# inwich.net
KiCad netlist of a schematic drawn in EAGLE
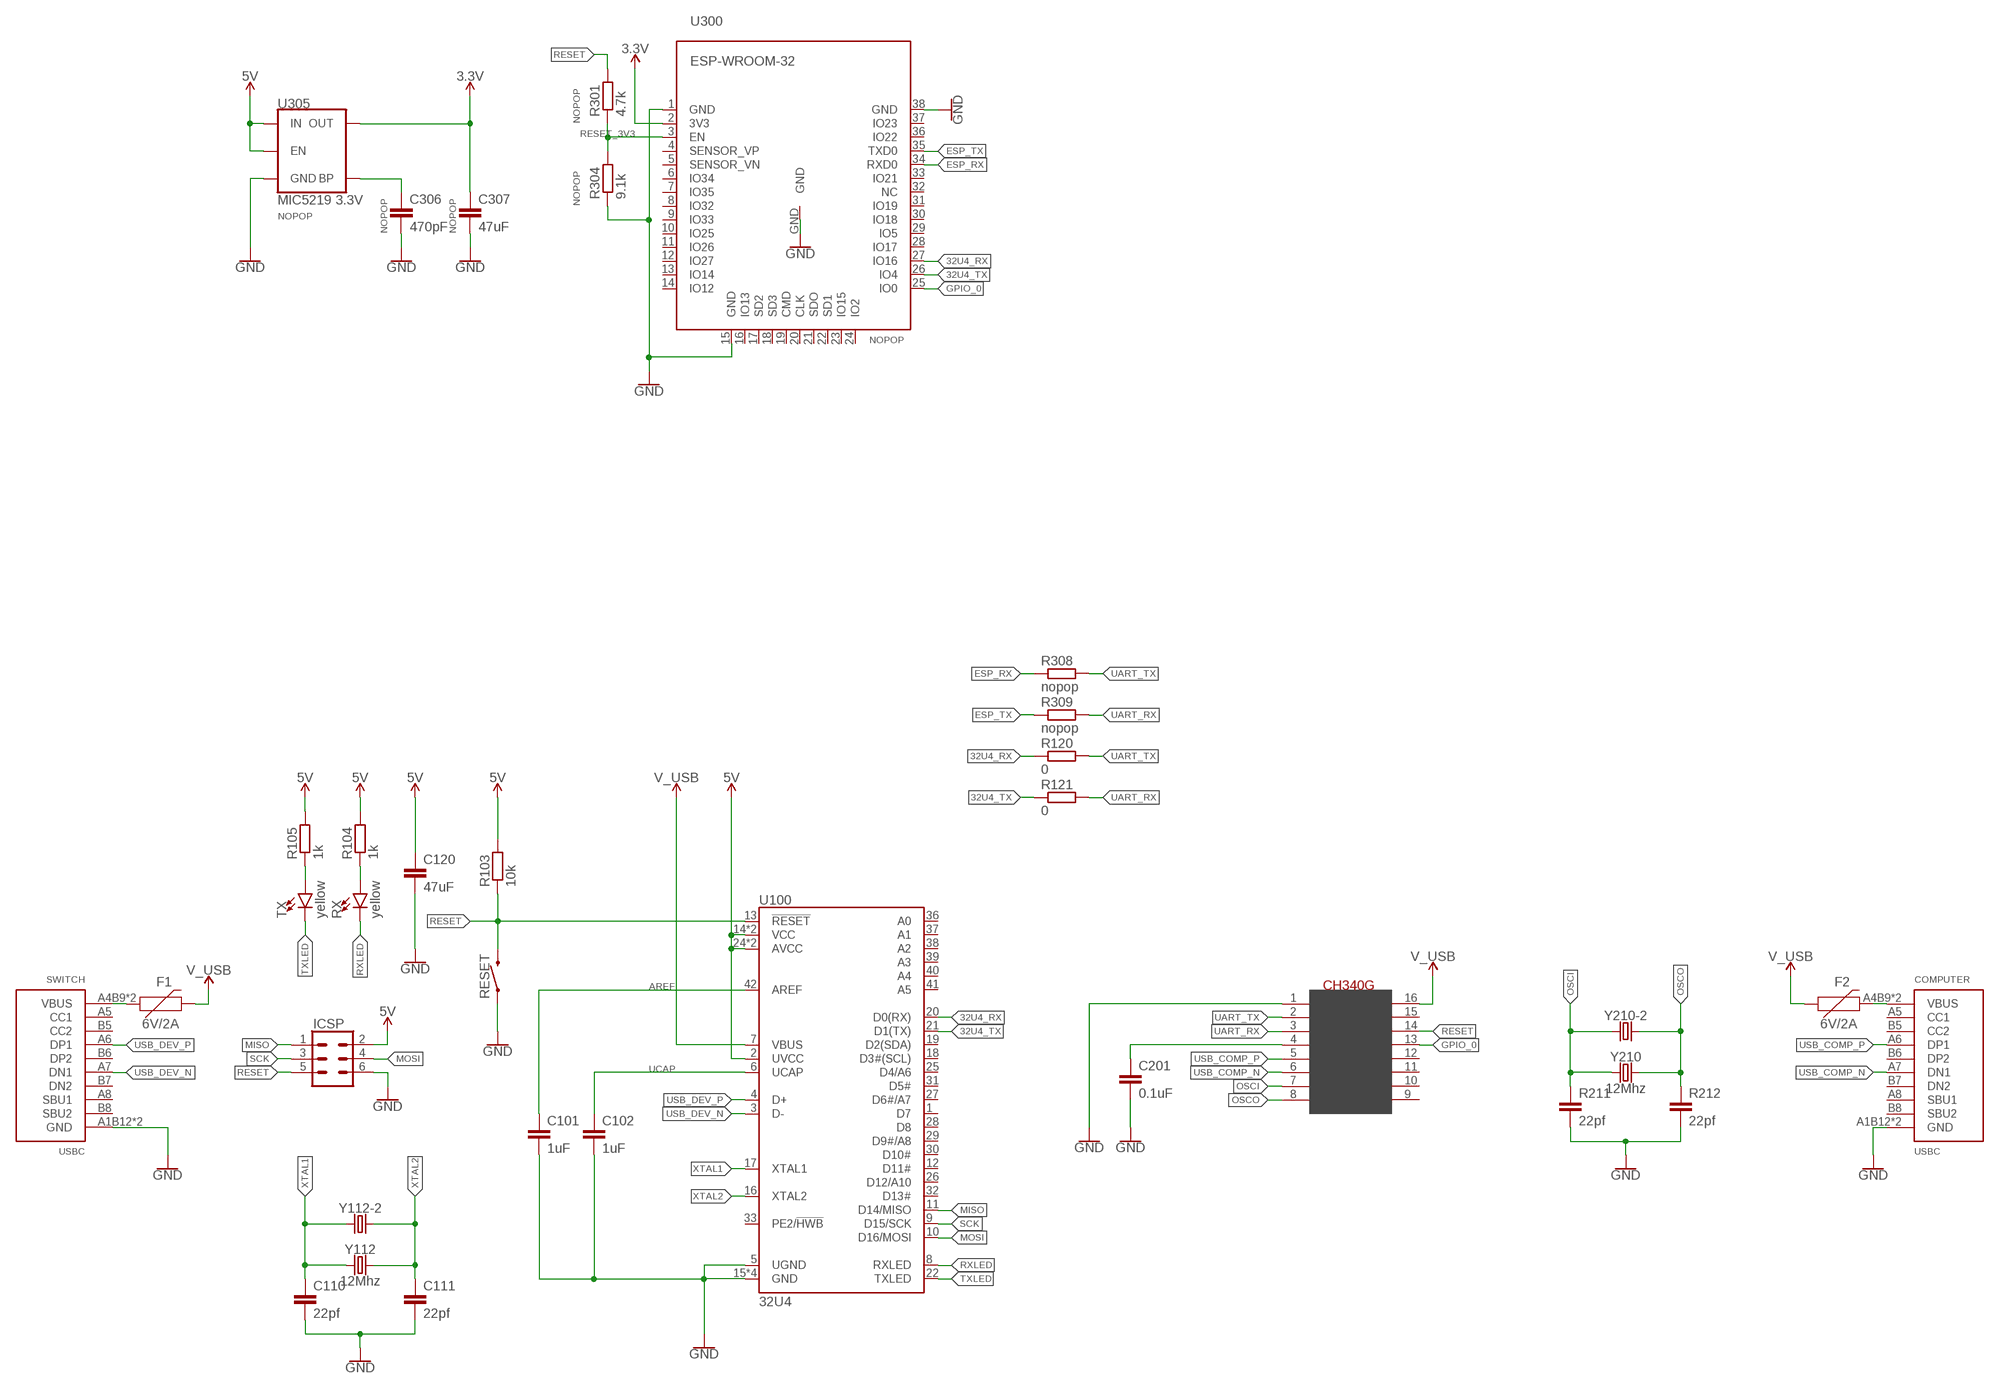
[diagram p0: schematic, sheet 1]

(export (version "E")
  (design (tool "Eeschema 10.0.6"))
  (components
    (comp (ref "C101")
      (value "1uF")
      (footprint "eagle-import:C0805")
      (libsource (lib "eagle-import") (part "C-EUC0805"))
    )
    (comp (ref "C102")
      (value "1uF")
      (footprint "eagle-import:C0805")
      (libsource (lib "eagle-import") (part "C-EUC0805"))
    )
    (comp (ref "C110")
      (value "22pf")
      (footprint "eagle-import:C0805")
      (libsource (lib "eagle-import") (part "C-EUC0805"))
    )
    (comp (ref "C111")
      (value "22pf")
      (footprint "eagle-import:C0805")
      (libsource (lib "eagle-import") (part "C-EUC0805"))
    )
    (comp (ref "C120")
      (value "47uF")
      (footprint "eagle-import:C0805")
      (libsource (lib "eagle-import") (part "C-EUC0805"))
    )
    (comp (ref "C201")
      (value "0.1uF")
      (footprint "eagle-import:C0805")
      (libsource (lib "eagle-import") (part "C-EUC0805"))
    )
    (comp (ref "C306")
      (value "470pF")
      (footprint "eagle-import:C0805")
      (libsource (lib "eagle-import") (part "C-EUC0805"))
    )
    (comp (ref "C307")
      (value "47uF")
      (footprint "eagle-import:C0805")
      (libsource (lib "eagle-import") (part "C-EUC0805"))
    )
    (comp (ref "COMPUTER")
      (value "USBC")
      (footprint "eagle-import:USBC")
      (libsource (lib "eagle-import") (part "USBC"))
    )
    (comp (ref "F1")
      (value "6V/2A")
      (footprint "eagle-import:1210")
      (libsource (lib "eagle-import") (part "PPTC_6V2A"))
    )
    (comp (ref "F2")
      (value "6V/2A")
      (footprint "eagle-import:1210")
      (libsource (lib "eagle-import") (part "PPTC_6V2A"))
    )
    (comp (ref "ICSP")
      (value "CONN_03X2SHROUD")
      (footprint "eagle-import:2X3-SHROUDED")
      (libsource (lib "eagle-import") (part "CONN_03X2SHROUD"))
    )
    (comp (ref "R103")
      (value "10k")
      (footprint "eagle-import:R0805")
      (libsource (lib "eagle-import") (part "R-EU_R0805"))
    )
    (comp (ref "R104")
      (value "1k")
      (footprint "eagle-import:R0805")
      (libsource (lib "eagle-import") (part "R-EU_R0805"))
    )
    (comp (ref "R105")
      (value "1k")
      (footprint "eagle-import:R0805")
      (libsource (lib "eagle-import") (part "R-EU_R0805"))
    )
    (comp (ref "R120")
      (value "0")
      (footprint "eagle-import:R0805")
      (libsource (lib "eagle-import") (part "R-EU_R0805"))
    )
    (comp (ref "R121")
      (value "0")
      (footprint "eagle-import:R0805")
      (libsource (lib "eagle-import") (part "R-EU_R0805"))
    )
    (comp (ref "R211")
      (value "22pf")
      (footprint "eagle-import:C0805")
      (libsource (lib "eagle-import") (part "C-EUC0805"))
    )
    (comp (ref "R212")
      (value "22pf")
      (footprint "eagle-import:C0805")
      (libsource (lib "eagle-import") (part "C-EUC0805"))
    )
    (comp (ref "R301")
      (value "4.7k")
      (footprint "eagle-import:R0805")
      (libsource (lib "eagle-import") (part "R-EU_R0805"))
    )
    (comp (ref "R304")
      (value "9.1k")
      (footprint "eagle-import:R0805")
      (libsource (lib "eagle-import") (part "R-EU_R0805"))
    )
    (comp (ref "R308")
      (value "nopop")
      (footprint "eagle-import:R0805")
      (libsource (lib "eagle-import") (part "R-EU_R0805"))
    )
    (comp (ref "R309")
      (value "nopop")
      (footprint "eagle-import:R0805")
      (libsource (lib "eagle-import") (part "R-EU_R0805"))
    )
    (comp (ref "RESET")
      (value "MOMENTARY-SWITCH-SPST-SMD-6.0X3.5MM")
      (footprint "eagle-import:TACTILE_SWITCH_SMD_6.0X3.5MM")
      (libsource (lib "eagle-import") (part "MOMENTARY-SWITCH-SPST-SMD-6.0X3.5MM"))
    )
    (comp (ref "RX")
      (value "yellow")
      (footprint "eagle-import:LED-1206")
      (libsource (lib "eagle-import") (part "LED1206"))
    )
    (comp (ref "SWITCH")
      (value "USBC")
      (footprint "eagle-import:USBC")
      (libsource (lib "eagle-import") (part "USBC"))
    )
    (comp (ref "TX")
      (value "yellow")
      (footprint "eagle-import:LED-1206")
      (libsource (lib "eagle-import") (part "LED1206"))
    )
    (comp (ref "U100")
      (value "32U4")
      (footprint "eagle-import:TQFP44")
      (libsource (lib "eagle-import") (part "ATMEGA32U4-ARDUINOTQFP-44"))
    )
    (comp (ref "U200")
      (value "CH340G")
      (footprint "eagle-import:SOIC16")
      (libsource (lib "eagle-import") (part "CH340G"))
    )
    (comp (ref "U300")
      (value "ESP-WROOM-32")
      (footprint "eagle-import:ESP-WROOM-32")
      (libsource (lib "eagle-import") (part "ESP-WROOM-32"))
    )
    (comp (ref "U305")
      (value "MIC5219 3.3V")
      (footprint "eagle-import:SOT23-5")
      (libsource (lib "eagle-import") (part "V_REG_MIC52193.3V"))
    )
    (comp (ref "Y112")
      (value "12Mhz")
      (footprint "eagle-import:HC49UP")
      (libsource (lib "eagle-import") (part "CRYSTALSMD-HC49UP"))
    )
    (comp (ref "Y112-2")
      (value "CRYSTALPTH-HC49UV")
      (footprint "eagle-import:HC49U")
      (libsource (lib "eagle-import") (part "CRYSTALPTH-HC49UV"))
    )
    (comp (ref "Y210")
      (value "12Mhz")
      (footprint "eagle-import:HC49UP")
      (libsource (lib "eagle-import") (part "CRYSTALSMD-HC49UP"))
    )
    (comp (ref "Y210-2")
      (value "CRYSTALPTH-HC49UV")
      (footprint "eagle-import:HC49U")
      (libsource (lib "eagle-import") (part "CRYSTALPTH-HC49UV"))
    )
  )
  (nets
    (net (code "1") (name "/AREF") (class "Default")
      (node (ref "C101") (pin "1") (pinfunction "1_1") (pintype "passive"))
      (node (ref "U100") (pin "42") (pinfunction "AREF_42") (pintype "bidirectional"))
    )
    (net (code "2") (name "/RESET_3V3") (class "Default")
      (node (ref "R301") (pin "1") (pinfunction "1_1") (pintype "passive"))
      (node (ref "R304") (pin "2") (pinfunction "2_2") (pintype "passive"))
      (node (ref "U300") (pin "3") (pinfunction "EN_3") (pintype "bidirectional"))
    )
    (net (code "3") (name "/UCAP") (class "Default")
      (node (ref "C102") (pin "1") (pinfunction "1_1") (pintype "passive"))
      (node (ref "U100") (pin "6") (pinfunction "UCAP_6") (pintype "bidirectional"))
    )
    (net (code "4") (name "3.3V") (class "Default")
      (node (ref "C307") (pin "1") (pinfunction "1_1") (pintype "passive"))
      (node (ref "U300") (pin "2") (pinfunction "3V3_2") (pintype "bidirectional"))
      (node (ref "U305") (pin "5") (pinfunction "OUT_5") (pintype "passive"))
    )
    (net (code "5") (name "5V") (class "Default")
      (node (ref "C120") (pin "1") (pinfunction "1_1") (pintype "passive"))
      (node (ref "ICSP") (pin "2") (pinfunction "2_2") (pintype "bidirectional"))
      (node (ref "R103") (pin "2") (pinfunction "2_2") (pintype "passive"))
      (node (ref "R104") (pin "2") (pinfunction "2_2") (pintype "passive"))
      (node (ref "R105") (pin "2") (pinfunction "2_2") (pintype "passive"))
      (node (ref "U100") (pin "14") (pinfunction "VCC_14") (pintype "bidirectional"))
      (node (ref "U100") (pin "2") (pinfunction "UVCC_2") (pintype "bidirectional"))
      (node (ref "U100") (pin "24") (pinfunction "AVCC_24") (pintype "bidirectional"))
      (node (ref "U100") (pin "34") (pinfunction "VCC_34") (pintype "bidirectional"))
      (node (ref "U100") (pin "44") (pinfunction "AVCC_44") (pintype "bidirectional"))
      (node (ref "U305") (pin "1") (pinfunction "IN_1") (pintype "input"))
      (node (ref "U305") (pin "3") (pinfunction "EN_3") (pintype "input"))
    )
    (net (code "6") (name "32U4_RX") (class "Default")
      (node (ref "R120") (pin "1") (pinfunction "1_1") (pintype "passive"))
      (node (ref "U100") (pin "20") (pinfunction "D0(RX)_20") (pintype "bidirectional"))
      (node (ref "U300") (pin "27") (pinfunction "IO16_27") (pintype "bidirectional"))
    )
    (net (code "7") (name "32U4_TX") (class "Default")
      (node (ref "R121") (pin "1") (pinfunction "1_1") (pintype "passive"))
      (node (ref "U100") (pin "21") (pinfunction "D1(TX)_21") (pintype "bidirectional"))
      (node (ref "U300") (pin "26") (pinfunction "IO4_26") (pintype "bidirectional"))
    )
    (net (code "8") (name "ESP_RX") (class "Default")
      (node (ref "R308") (pin "1") (pinfunction "1_1") (pintype "passive"))
      (node (ref "U300") (pin "34") (pinfunction "RXD0_34") (pintype "bidirectional"))
    )
    (net (code "9") (name "ESP_TX") (class "Default")
      (node (ref "R309") (pin "1") (pinfunction "1_1") (pintype "passive"))
      (node (ref "U300") (pin "35") (pinfunction "TXD0_35") (pintype "bidirectional"))
    )
    (net (code "10") (name "GND") (class "Default")
      (node (ref "C101") (pin "2") (pinfunction "2_2") (pintype "passive"))
      (node (ref "C102") (pin "2") (pinfunction "2_2") (pintype "passive"))
      (node (ref "C110") (pin "2") (pinfunction "2_2") (pintype "passive"))
      (node (ref "C111") (pin "2") (pinfunction "2_2") (pintype "passive"))
      (node (ref "C120") (pin "2") (pinfunction "2_2") (pintype "passive"))
      (node (ref "C201") (pin "2") (pinfunction "2_2") (pintype "passive"))
      (node (ref "C306") (pin "2") (pinfunction "2_2") (pintype "passive"))
      (node (ref "C307") (pin "2") (pinfunction "2_2") (pintype "passive"))
      (node (ref "COMPUTER") (pin "A1B12") (pinfunction "GND_A1B12") (pintype "bidirectional"))
      (node (ref "COMPUTER") (pin "B1A12") (pinfunction "GND_B1A12") (pintype "bidirectional"))
      (node (ref "ICSP") (pin "6") (pinfunction "6_6") (pintype "bidirectional"))
      (node (ref "R211") (pin "2") (pinfunction "2_2") (pintype "passive"))
      (node (ref "R212") (pin "2") (pinfunction "2_2") (pintype "passive"))
      (node (ref "R304") (pin "1") (pinfunction "1_1") (pintype "passive"))
      (node (ref "RESET") (pin "1") (pinfunction "1_1") (pintype "passive"))
      (node (ref "SWITCH") (pin "A1B12") (pinfunction "GND_A1B12") (pintype "bidirectional"))
      (node (ref "SWITCH") (pin "B1A12") (pinfunction "GND_B1A12") (pintype "bidirectional"))
      (node (ref "U100") (pin "15") (pinfunction "GND_15") (pintype "bidirectional"))
      (node (ref "U100") (pin "23") (pinfunction "GND_23") (pintype "bidirectional"))
      (node (ref "U100") (pin "35") (pinfunction "GND_35") (pintype "bidirectional"))
      (node (ref "U100") (pin "43") (pinfunction "GND_43") (pintype "bidirectional"))
      (node (ref "U100") (pin "5") (pinfunction "UGND_5") (pintype "bidirectional"))
      (node (ref "U200") (pin "1") (pinfunction "GND_1") (pintype "bidirectional"))
      (node (ref "U300") (pin "1") (pinfunction "GND_1") (pintype "bidirectional"))
      (node (ref "U300") (pin "15") (pinfunction "GND_15") (pintype "bidirectional"))
      (node (ref "U300") (pin "38") (pinfunction "GND_38") (pintype "bidirectional"))
      (node (ref "U300") (pin "GND") (pinfunction "GND_GND") (pintype "bidirectional"))
      (node (ref "U305") (pin "2") (pinfunction "GND_2") (pintype "input"))
    )
    (net (code "11") (name "GPIO_0") (class "Default")
      (node (ref "U200") (pin "13") (pinfunction "DTR_13") (pintype "bidirectional"))
      (node (ref "U300") (pin "25") (pinfunction "IO0_25") (pintype "bidirectional"))
    )
    (net (code "12") (name "MISO") (class "Default")
      (node (ref "ICSP") (pin "1") (pinfunction "1_1") (pintype "bidirectional"))
      (node (ref "U100") (pin "11") (pinfunction "D14/MISO_11") (pintype "bidirectional"))
    )
    (net (code "13") (name "MOSI") (class "Default")
      (node (ref "ICSP") (pin "4") (pinfunction "4_4") (pintype "bidirectional"))
      (node (ref "U100") (pin "10") (pinfunction "D16/MOSI_10") (pintype "bidirectional"))
    )
    (net (code "14") (name "Net-(COMPUTER-VBUS-PadA4B9)") (class "Default")
      (node (ref "COMPUTER") (pin "A4B9") (pinfunction "VBUS_A4B9") (pintype "bidirectional"))
      (node (ref "COMPUTER") (pin "B4A9") (pinfunction "VBUS_B4A9") (pintype "bidirectional"))
      (node (ref "F2") (pin "2") (pinfunction "2_2") (pintype "bidirectional"))
    )
    (net (code "15") (name "Net-(F1-Pad1)") (class "Default")
      (node (ref "F1") (pin "1") (pinfunction "1_1") (pintype "bidirectional"))
      (node (ref "SWITCH") (pin "A4B9") (pinfunction "VBUS_A4B9") (pintype "bidirectional"))
      (node (ref "SWITCH") (pin "B4A9") (pinfunction "VBUS_B4A9") (pintype "bidirectional"))
    )
    (net (code "16") (name "Net-(R104-Pad1)") (class "Default")
      (node (ref "R104") (pin "1") (pinfunction "1_1") (pintype "passive"))
      (node (ref "RX") (pin "A") (pinfunction "A_A") (pintype "passive"))
    )
    (net (code "17") (name "Net-(R105-Pad1)") (class "Default")
      (node (ref "R105") (pin "1") (pinfunction "1_1") (pintype "passive"))
      (node (ref "TX") (pin "A") (pinfunction "A_A") (pintype "passive"))
    )
    (net (code "18") (name "Net-(U200-V3)") (class "Default")
      (node (ref "C201") (pin "1") (pinfunction "1_1") (pintype "passive"))
      (node (ref "U200") (pin "4") (pinfunction "V3_4") (pintype "bidirectional"))
    )
    (net (code "19") (name "Net-(U305-BP)") (class "Default")
      (node (ref "C306") (pin "1") (pinfunction "1_1") (pintype "passive"))
      (node (ref "U305") (pin "4") (pinfunction "BP_4") (pintype "input"))
    )
    (net (code "20") (name "OSCI") (class "Default")
      (node (ref "R211") (pin "1") (pinfunction "1_1") (pintype "passive"))
      (node (ref "U200") (pin "7") (pinfunction "XI_7") (pintype "bidirectional"))
      (node (ref "Y210") (pin "1") (pinfunction "1_1") (pintype "passive"))
      (node (ref "Y210-2") (pin "1") (pinfunction "1_1") (pintype "passive"))
    )
    (net (code "21") (name "OSCO") (class "Default")
      (node (ref "R212") (pin "1") (pinfunction "1_1") (pintype "passive"))
      (node (ref "U200") (pin "8") (pinfunction "XO_8") (pintype "bidirectional"))
      (node (ref "Y210") (pin "2") (pinfunction "2_2") (pintype "passive"))
      (node (ref "Y210-2") (pin "2") (pinfunction "2_2") (pintype "passive"))
    )
    (net (code "22") (name "RESET") (class "Default")
      (node (ref "ICSP") (pin "5") (pinfunction "5_5") (pintype "bidirectional"))
      (node (ref "R103") (pin "1") (pinfunction "1_1") (pintype "passive"))
      (node (ref "R301") (pin "2") (pinfunction "2_2") (pintype "passive"))
      (node (ref "RESET") (pin "2") (pinfunction "2_2") (pintype "passive"))
      (node (ref "U100") (pin "13") (pinfunction "~{RESET}_13") (pintype "bidirectional"))
      (node (ref "U200") (pin "14") (pinfunction "RTS_14") (pintype "bidirectional"))
    )
    (net (code "23") (name "RXLED") (class "Default")
      (node (ref "RX") (pin "C") (pinfunction "C_C") (pintype "passive"))
      (node (ref "U100") (pin "8") (pinfunction "RXLED_8") (pintype "bidirectional"))
    )
    (net (code "24") (name "SCK") (class "Default")
      (node (ref "ICSP") (pin "3") (pinfunction "3_3") (pintype "bidirectional"))
      (node (ref "U100") (pin "9") (pinfunction "D15/SCK_9") (pintype "bidirectional"))
    )
    (net (code "25") (name "TXLED") (class "Default")
      (node (ref "TX") (pin "C") (pinfunction "C_C") (pintype "passive"))
      (node (ref "U100") (pin "22") (pinfunction "TXLED_22") (pintype "bidirectional"))
    )
    (net (code "26") (name "UART_RX") (class "Default")
      (node (ref "R121") (pin "2") (pinfunction "2_2") (pintype "passive"))
      (node (ref "R309") (pin "2") (pinfunction "2_2") (pintype "passive"))
      (node (ref "U200") (pin "3") (pinfunction "RX_3") (pintype "bidirectional"))
    )
    (net (code "27") (name "UART_TX") (class "Default")
      (node (ref "R120") (pin "2") (pinfunction "2_2") (pintype "passive"))
      (node (ref "R308") (pin "2") (pinfunction "2_2") (pintype "passive"))
      (node (ref "U200") (pin "2") (pinfunction "TX_2") (pintype "bidirectional"))
    )
    (net (code "28") (name "USB_COMP_N") (class "Default")
      (node (ref "COMPUTER") (pin "A7") (pinfunction "DN1_A7") (pintype "bidirectional"))
      (node (ref "U200") (pin "6") (pinfunction "D-_6") (pintype "bidirectional"))
    )
    (net (code "29") (name "USB_COMP_P") (class "Default")
      (node (ref "COMPUTER") (pin "A6") (pinfunction "DP1_A6") (pintype "bidirectional"))
      (node (ref "U200") (pin "5") (pinfunction "D+_5") (pintype "bidirectional"))
    )
    (net (code "30") (name "USB_DEV_N") (class "Default")
      (node (ref "SWITCH") (pin "A7") (pinfunction "DN1_A7") (pintype "bidirectional"))
      (node (ref "U100") (pin "3") (pinfunction "D-_3") (pintype "bidirectional"))
    )
    (net (code "31") (name "USB_DEV_P") (class "Default")
      (node (ref "SWITCH") (pin "A6") (pinfunction "DP1_A6") (pintype "bidirectional"))
      (node (ref "U100") (pin "4") (pinfunction "D+_4") (pintype "bidirectional"))
    )
    (net (code "32") (name "V_USB") (class "Default")
      (node (ref "F1") (pin "2") (pinfunction "2_2") (pintype "bidirectional"))
      (node (ref "F2") (pin "1") (pinfunction "1_1") (pintype "bidirectional"))
      (node (ref "U100") (pin "7") (pinfunction "VBUS_7") (pintype "bidirectional"))
      (node (ref "U200") (pin "16") (pinfunction "VCC_16") (pintype "bidirectional"))
    )
    (net (code "33") (name "XTAL1") (class "Default")
      (node (ref "C110") (pin "1") (pinfunction "1_1") (pintype "passive"))
      (node (ref "U100") (pin "17") (pinfunction "XTAL1_17") (pintype "bidirectional"))
      (node (ref "Y112") (pin "1") (pinfunction "1_1") (pintype "passive"))
      (node (ref "Y112-2") (pin "1") (pinfunction "1_1") (pintype "passive"))
    )
    (net (code "34") (name "XTAL2") (class "Default")
      (node (ref "C111") (pin "1") (pinfunction "1_1") (pintype "passive"))
      (node (ref "U100") (pin "16") (pinfunction "XTAL2_16") (pintype "bidirectional"))
      (node (ref "Y112") (pin "2") (pinfunction "2_2") (pintype "passive"))
      (node (ref "Y112-2") (pin "2") (pinfunction "2_2") (pintype "passive"))
    )
    (net (code "35") (name "unconnected-(COMPUTER-CC1-PadA5)") (class "Default")
      (node (ref "COMPUTER") (pin "A5") (pinfunction "CC1_A5") (pintype "bidirectional"))
    )
    (net (code "36") (name "unconnected-(COMPUTER-CC2-PadB5)") (class "Default")
      (node (ref "COMPUTER") (pin "B5") (pinfunction "CC2_B5") (pintype "bidirectional"))
    )
    (net (code "37") (name "unconnected-(COMPUTER-DN2-PadB7)") (class "Default")
      (node (ref "COMPUTER") (pin "B7") (pinfunction "DN2_B7") (pintype "bidirectional"))
    )
    (net (code "38") (name "unconnected-(COMPUTER-DP2-PadB6)") (class "Default")
      (node (ref "COMPUTER") (pin "B6") (pinfunction "DP2_B6") (pintype "bidirectional"))
    )
    (net (code "39") (name "unconnected-(COMPUTER-SBU1-PadA8)") (class "Default")
      (node (ref "COMPUTER") (pin "A8") (pinfunction "SBU1_A8") (pintype "bidirectional"))
    )
    (net (code "40") (name "unconnected-(COMPUTER-SBU2-PadB8)") (class "Default")
      (node (ref "COMPUTER") (pin "B8") (pinfunction "SBU2_B8") (pintype "bidirectional"))
    )
    (net (code "41") (name "unconnected-(SWITCH-CC1-PadA5)") (class "Default")
      (node (ref "SWITCH") (pin "A5") (pinfunction "CC1_A5") (pintype "bidirectional"))
    )
    (net (code "42") (name "unconnected-(SWITCH-CC2-PadB5)") (class "Default")
      (node (ref "SWITCH") (pin "B5") (pinfunction "CC2_B5") (pintype "bidirectional"))
    )
    (net (code "43") (name "unconnected-(SWITCH-DN2-PadB7)") (class "Default")
      (node (ref "SWITCH") (pin "B7") (pinfunction "DN2_B7") (pintype "bidirectional"))
    )
    (net (code "44") (name "unconnected-(SWITCH-DP2-PadB6)") (class "Default")
      (node (ref "SWITCH") (pin "B6") (pinfunction "DP2_B6") (pintype "bidirectional"))
    )
    (net (code "45") (name "unconnected-(SWITCH-SBU1-PadA8)") (class "Default")
      (node (ref "SWITCH") (pin "A8") (pinfunction "SBU1_A8") (pintype "bidirectional"))
    )
    (net (code "46") (name "unconnected-(SWITCH-SBU2-PadB8)") (class "Default")
      (node (ref "SWITCH") (pin "B8") (pinfunction "SBU2_B8") (pintype "bidirectional"))
    )
    (net (code "47") (name "unconnected-(U100-A0-Pad36)") (class "Default")
      (node (ref "U100") (pin "36") (pinfunction "A0_36") (pintype "bidirectional"))
    )
    (net (code "48") (name "unconnected-(U100-A1-Pad37)") (class "Default")
      (node (ref "U100") (pin "37") (pinfunction "A1_37") (pintype "bidirectional"))
    )
    (net (code "49") (name "unconnected-(U100-A2-Pad38)") (class "Default")
      (node (ref "U100") (pin "38") (pinfunction "A2_38") (pintype "bidirectional"))
    )
    (net (code "50") (name "unconnected-(U100-A3-Pad39)") (class "Default")
      (node (ref "U100") (pin "39") (pinfunction "A3_39") (pintype "bidirectional"))
    )
    (net (code "51") (name "unconnected-(U100-A4-Pad40)") (class "Default")
      (node (ref "U100") (pin "40") (pinfunction "A4_40") (pintype "bidirectional"))
    )
    (net (code "52") (name "unconnected-(U100-A5-Pad41)") (class "Default")
      (node (ref "U100") (pin "41") (pinfunction "A5_41") (pintype "bidirectional"))
    )
    (net (code "53") (name "unconnected-(U100-D2(SDA)-Pad19)") (class "Default")
      (node (ref "U100") (pin "19") (pinfunction "D2(SDA)_19") (pintype "bidirectional"))
    )
    (net (code "54") (name "unconnected-(U100-D3#(SCL)-Pad18)") (class "Default")
      (node (ref "U100") (pin "18") (pinfunction "D3#(SCL)_18") (pintype "bidirectional"))
    )
    (net (code "55") (name "unconnected-(U100-D4{slash}A6-Pad25)") (class "Default")
      (node (ref "U100") (pin "25") (pinfunction "D4/A6_25") (pintype "bidirectional"))
    )
    (net (code "56") (name "unconnected-(U100-D5#-Pad31)") (class "Default")
      (node (ref "U100") (pin "31") (pinfunction "D5#_31") (pintype "bidirectional"))
    )
    (net (code "57") (name "unconnected-(U100-D6#{slash}A7-Pad27)") (class "Default")
      (node (ref "U100") (pin "27") (pinfunction "D6#/A7_27") (pintype "bidirectional"))
    )
    (net (code "58") (name "unconnected-(U100-D7-Pad1)") (class "Default")
      (node (ref "U100") (pin "1") (pinfunction "D7_1") (pintype "bidirectional"))
    )
    (net (code "59") (name "unconnected-(U100-D8-Pad28)") (class "Default")
      (node (ref "U100") (pin "28") (pinfunction "D8_28") (pintype "bidirectional"))
    )
    (net (code "60") (name "unconnected-(U100-D9#{slash}A8-Pad29)") (class "Default")
      (node (ref "U100") (pin "29") (pinfunction "D9#/A8_29") (pintype "bidirectional"))
    )
    (net (code "61") (name "unconnected-(U100-D10#-Pad30)") (class "Default")
      (node (ref "U100") (pin "30") (pinfunction "D10#_30") (pintype "bidirectional"))
    )
    (net (code "62") (name "unconnected-(U100-D11#-Pad12)") (class "Default")
      (node (ref "U100") (pin "12") (pinfunction "D11#_12") (pintype "bidirectional"))
    )
    (net (code "63") (name "unconnected-(U100-D12{slash}A10-Pad26)") (class "Default")
      (node (ref "U100") (pin "26") (pinfunction "D12/A10_26") (pintype "bidirectional"))
    )
    (net (code "64") (name "unconnected-(U100-D13#-Pad32)") (class "Default")
      (node (ref "U100") (pin "32") (pinfunction "D13#_32") (pintype "bidirectional"))
    )
    (net (code "65") (name "unconnected-(U100-PE2{slash}~{HWB}-Pad33)") (class "Default")
      (node (ref "U100") (pin "33") (pinfunction "PE2/~{HWB}_33") (pintype "bidirectional"))
    )
    (net (code "66") (name "unconnected-(U200-CTS-Pad9)") (class "Default")
      (node (ref "U200") (pin "9") (pinfunction "CTS_9") (pintype "bidirectional"))
    )
    (net (code "67") (name "unconnected-(U200-DCD-Pad12)") (class "Default")
      (node (ref "U200") (pin "12") (pinfunction "DCD_12") (pintype "bidirectional"))
    )
    (net (code "68") (name "unconnected-(U200-DSR-Pad10)") (class "Default")
      (node (ref "U200") (pin "10") (pinfunction "DSR_10") (pintype "bidirectional"))
    )
    (net (code "69") (name "unconnected-(U200-RI-Pad11)") (class "Default")
      (node (ref "U200") (pin "11") (pinfunction "RI_11") (pintype "bidirectional"))
    )
    (net (code "70") (name "unconnected-(U200-RS232-Pad15)") (class "Default")
      (node (ref "U200") (pin "15") (pinfunction "RS232_15") (pintype "bidirectional"))
    )
    (net (code "71") (name "unconnected-(U300-CLK-Pad20)") (class "Default")
      (node (ref "U300") (pin "20") (pinfunction "CLK_20") (pintype "bidirectional"))
    )
    (net (code "72") (name "unconnected-(U300-CMD-Pad19)") (class "Default")
      (node (ref "U300") (pin "19") (pinfunction "CMD_19") (pintype "bidirectional"))
    )
    (net (code "73") (name "unconnected-(U300-IO2-Pad24)") (class "Default")
      (node (ref "U300") (pin "24") (pinfunction "IO2_24") (pintype "bidirectional"))
    )
    (net (code "74") (name "unconnected-(U300-IO5-Pad29)") (class "Default")
      (node (ref "U300") (pin "29") (pinfunction "IO5_29") (pintype "bidirectional"))
    )
    (net (code "75") (name "unconnected-(U300-IO12-Pad14)") (class "Default")
      (node (ref "U300") (pin "14") (pinfunction "IO12_14") (pintype "bidirectional"))
    )
    (net (code "76") (name "unconnected-(U300-IO13-Pad16)") (class "Default")
      (node (ref "U300") (pin "16") (pinfunction "IO13_16") (pintype "bidirectional"))
    )
    (net (code "77") (name "unconnected-(U300-IO14-Pad13)") (class "Default")
      (node (ref "U300") (pin "13") (pinfunction "IO14_13") (pintype "bidirectional"))
    )
    (net (code "78") (name "unconnected-(U300-IO15-Pad23)") (class "Default")
      (node (ref "U300") (pin "23") (pinfunction "IO15_23") (pintype "bidirectional"))
    )
    (net (code "79") (name "unconnected-(U300-IO17-Pad28)") (class "Default")
      (node (ref "U300") (pin "28") (pinfunction "IO17_28") (pintype "bidirectional"))
    )
    (net (code "80") (name "unconnected-(U300-IO18-Pad30)") (class "Default")
      (node (ref "U300") (pin "30") (pinfunction "IO18_30") (pintype "bidirectional"))
    )
    (net (code "81") (name "unconnected-(U300-IO19-Pad31)") (class "Default")
      (node (ref "U300") (pin "31") (pinfunction "IO19_31") (pintype "bidirectional"))
    )
    (net (code "82") (name "unconnected-(U300-IO21-Pad33)") (class "Default")
      (node (ref "U300") (pin "33") (pinfunction "IO21_33") (pintype "bidirectional"))
    )
    (net (code "83") (name "unconnected-(U300-IO22-Pad36)") (class "Default")
      (node (ref "U300") (pin "36") (pinfunction "IO22_36") (pintype "bidirectional"))
    )
    (net (code "84") (name "unconnected-(U300-IO23-Pad37)") (class "Default")
      (node (ref "U300") (pin "37") (pinfunction "IO23_37") (pintype "bidirectional"))
    )
    (net (code "85") (name "unconnected-(U300-IO25-Pad10)") (class "Default")
      (node (ref "U300") (pin "10") (pinfunction "IO25_10") (pintype "bidirectional"))
    )
    (net (code "86") (name "unconnected-(U300-IO26-Pad11)") (class "Default")
      (node (ref "U300") (pin "11") (pinfunction "IO26_11") (pintype "bidirectional"))
    )
    (net (code "87") (name "unconnected-(U300-IO27-Pad12)") (class "Default")
      (node (ref "U300") (pin "12") (pinfunction "IO27_12") (pintype "bidirectional"))
    )
    (net (code "88") (name "unconnected-(U300-IO32-Pad8)") (class "Default")
      (node (ref "U300") (pin "8") (pinfunction "IO32_8") (pintype "bidirectional"))
    )
    (net (code "89") (name "unconnected-(U300-IO33-Pad9)") (class "Default")
      (node (ref "U300") (pin "9") (pinfunction "IO33_9") (pintype "bidirectional"))
    )
    (net (code "90") (name "unconnected-(U300-IO34-Pad6)") (class "Default")
      (node (ref "U300") (pin "6") (pinfunction "IO34_6") (pintype "bidirectional"))
    )
    (net (code "91") (name "unconnected-(U300-IO35-Pad7)") (class "Default")
      (node (ref "U300") (pin "7") (pinfunction "IO35_7") (pintype "bidirectional"))
    )
    (net (code "92") (name "unconnected-(U300-NC-Pad32)") (class "Default")
      (node (ref "U300") (pin "32") (pinfunction "NC_32") (pintype "bidirectional"))
    )
    (net (code "93") (name "unconnected-(U300-SD1-Pad22)") (class "Default")
      (node (ref "U300") (pin "22") (pinfunction "SD1_22") (pintype "bidirectional"))
    )
    (net (code "94") (name "unconnected-(U300-SD2-Pad17)") (class "Default")
      (node (ref "U300") (pin "17") (pinfunction "SD2_17") (pintype "bidirectional"))
    )
    (net (code "95") (name "unconnected-(U300-SD3-Pad18)") (class "Default")
      (node (ref "U300") (pin "18") (pinfunction "SD3_18") (pintype "bidirectional"))
    )
    (net (code "96") (name "unconnected-(U300-SDO-Pad21)") (class "Default")
      (node (ref "U300") (pin "21") (pinfunction "SDO_21") (pintype "bidirectional"))
    )
    (net (code "97") (name "unconnected-(U300-SENSOR_VN-Pad5)") (class "Default")
      (node (ref "U300") (pin "5") (pinfunction "SENSOR_VN_5") (pintype "bidirectional"))
    )
    (net (code "98") (name "unconnected-(U300-SENSOR_VP-Pad4)") (class "Default")
      (node (ref "U300") (pin "4") (pinfunction "SENSOR_VP_4") (pintype "bidirectional"))
    )
  )
)
